# Main.net
KiCad netlist of a schematic drawn in Altium Designer
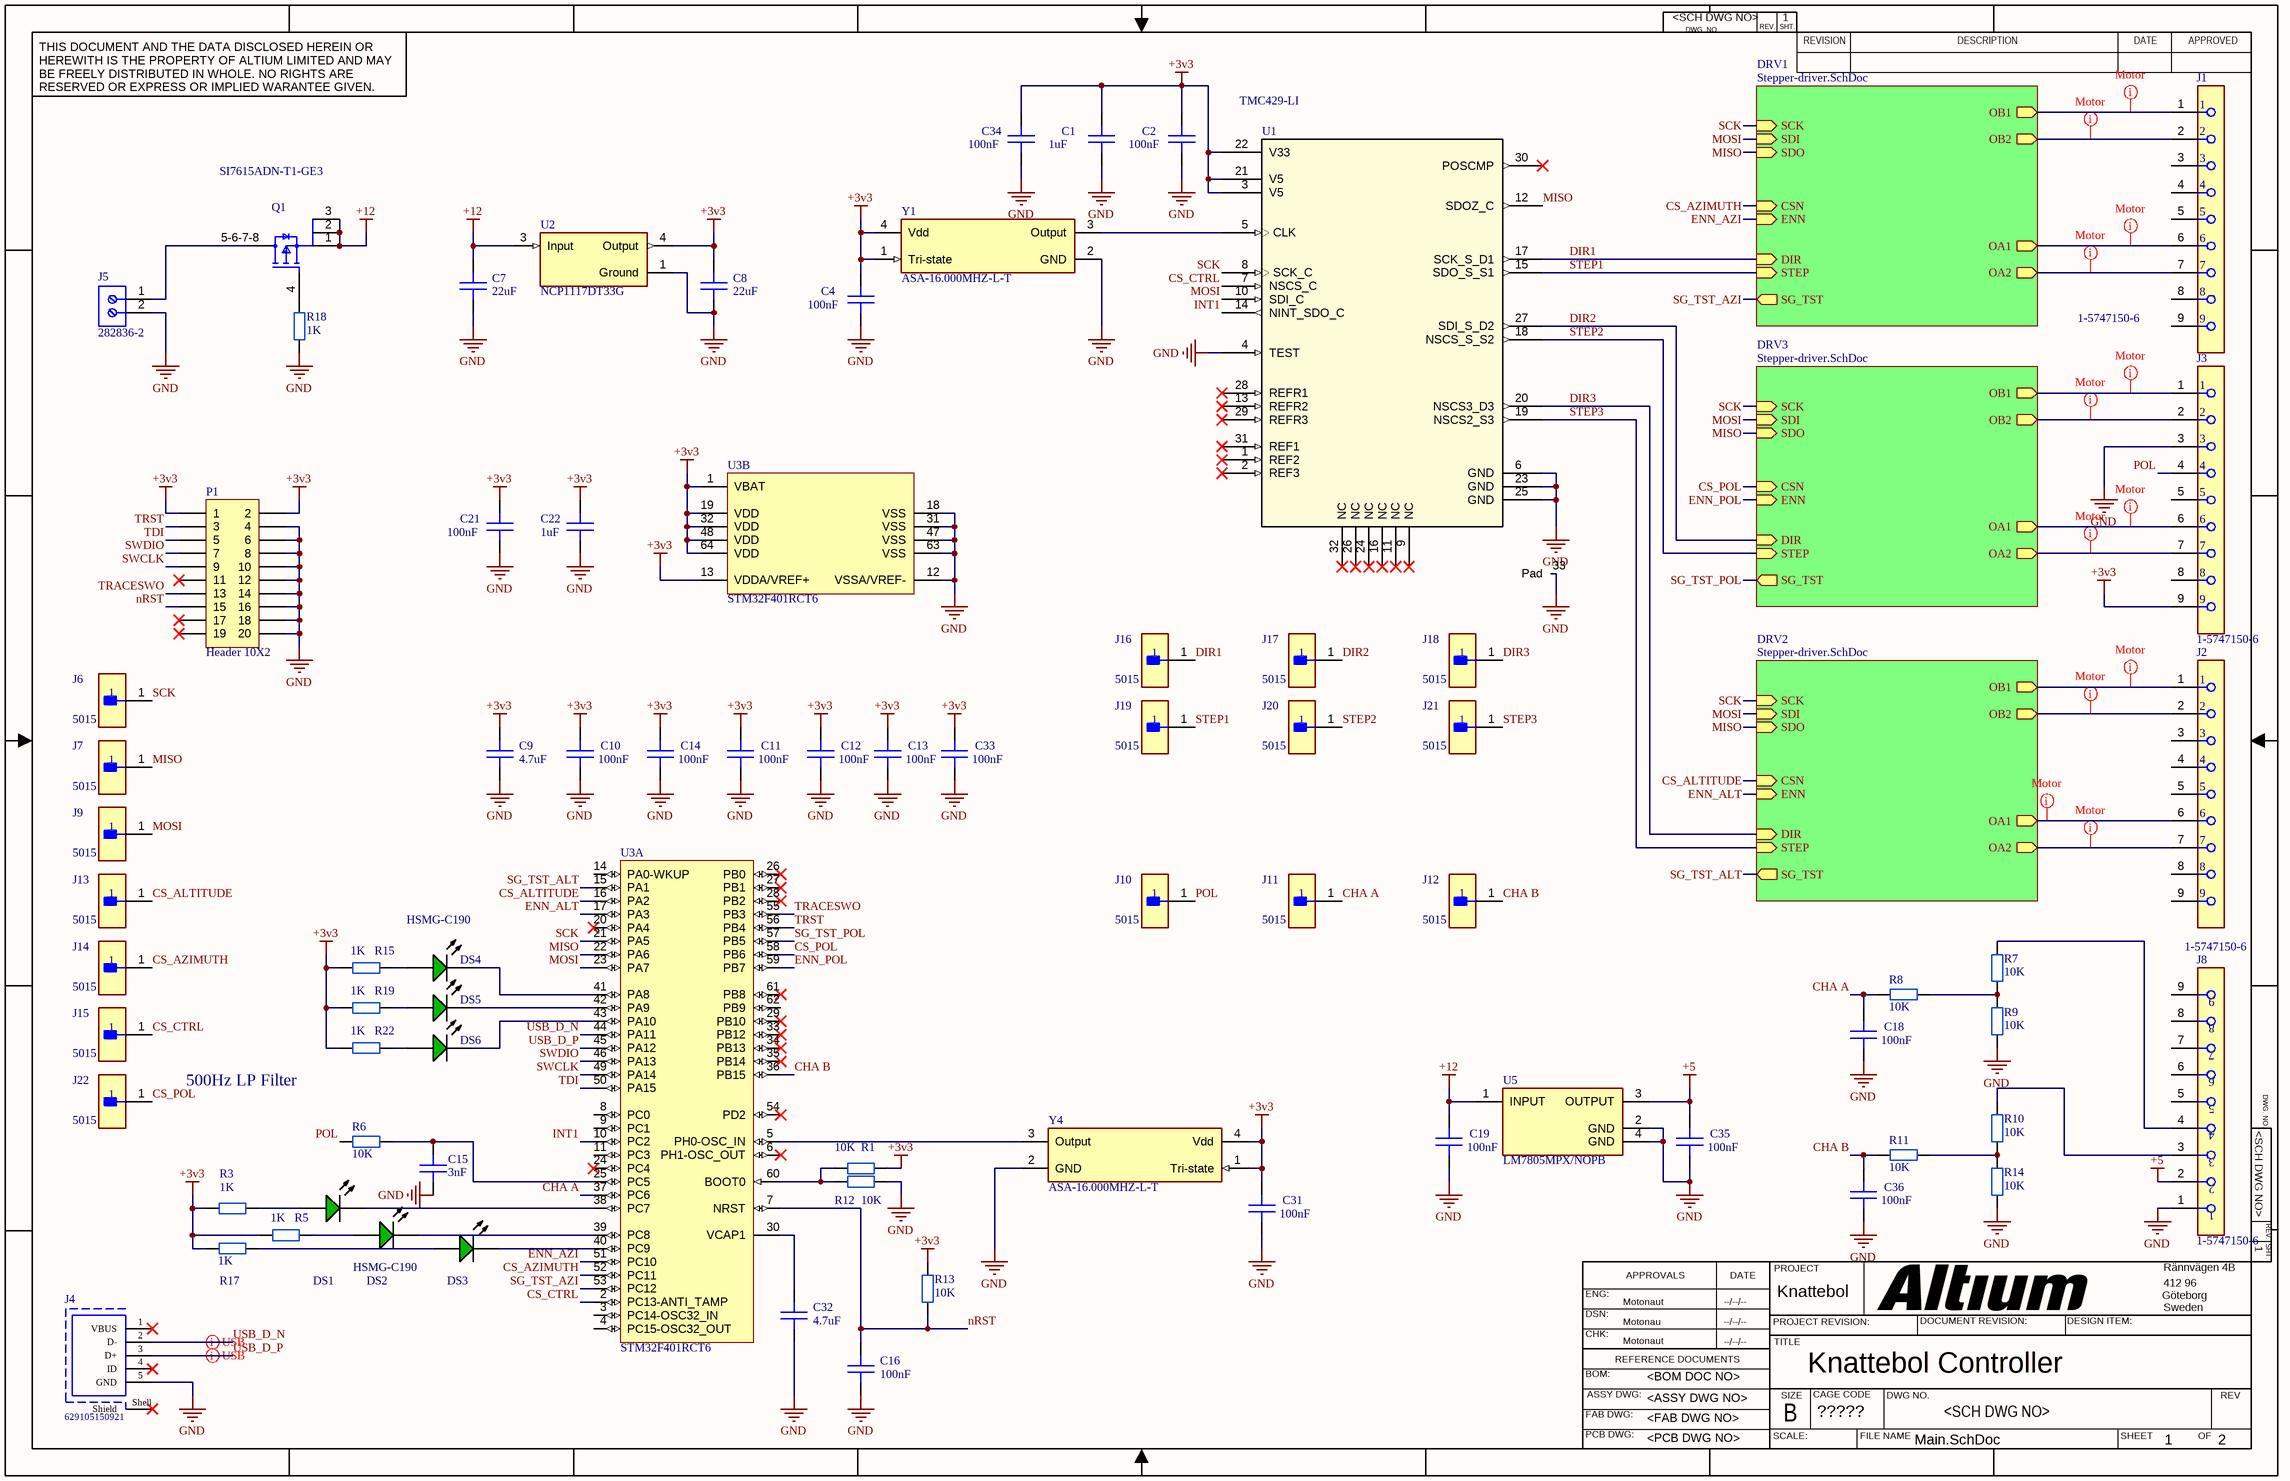
[diagram p0: Main.SchDoc]

(export (version "E")
  (design (tool "Eeschema 10.0.6"))
  (components
    (comp (ref "C1")
      (value "1uF")
      (footprint "C0603 (1608)")
      (fields (field (name "Comment") "Cap SMD"))
      (libsource (lib "Moto Symbol Lib") (part "Cap SMD"))
    )
    (comp (ref "C2")
      (value "100nF")
      (footprint "C0603 (1608)")
      (fields (field (name "Comment") "Cap SMD"))
      (libsource (lib "Moto Symbol Lib") (part "Cap SMD"))
    )
    (comp (ref "C4")
      (value "100nF")
      (footprint "C0603 (1608)")
      (fields (field (name "Comment") "Cap SMD"))
      (libsource (lib "Moto Symbol Lib") (part "Cap SMD"))
    )
    (comp (ref "C7")
      (value "22uF")
      (footprint "C0603 (1608)")
      (fields (field (name "Comment") "Cap SMD"))
      (libsource (lib "Moto Symbol Lib") (part "Cap SMD"))
    )
    (comp (ref "C8")
      (value "22uF")
      (footprint "C0603 (1608)")
      (fields (field (name "Comment") "Cap SMD"))
      (libsource (lib "Moto Symbol Lib") (part "Cap SMD"))
    )
    (comp (ref "C9")
      (value "4.7uF")
      (footprint "C0603 (1608)")
      (fields (field (name "Comment") "Cap SMD"))
      (libsource (lib "Moto Symbol Lib") (part "Cap SMD"))
    )
    (comp (ref "C10")
      (value "100nF")
      (footprint "C0603 (1608)")
      (fields (field (name "Comment") "Cap SMD"))
      (libsource (lib "Moto Symbol Lib") (part "Cap SMD"))
    )
    (comp (ref "C11")
      (value "100nF")
      (footprint "C0603 (1608)")
      (fields (field (name "Comment") "Cap SMD"))
      (libsource (lib "Moto Symbol Lib") (part "Cap SMD"))
    )
    (comp (ref "C12")
      (value "100nF")
      (footprint "C0603 (1608)")
      (fields (field (name "Comment") "Cap SMD"))
      (libsource (lib "Moto Symbol Lib") (part "Cap SMD"))
    )
    (comp (ref "C13")
      (value "100nF")
      (footprint "C0603 (1608)")
      (fields (field (name "Comment") "Cap SMD"))
      (libsource (lib "Moto Symbol Lib") (part "Cap SMD"))
    )
    (comp (ref "C14")
      (value "100nF")
      (footprint "C0603 (1608)")
      (fields (field (name "Comment") "Cap SMD"))
      (libsource (lib "Moto Symbol Lib") (part "Cap SMD"))
    )
    (comp (ref "C15")
      (value "3nF")
      (footprint "C0603 (1608)")
      (fields (field (name "Comment") "Cap SMD"))
      (libsource (lib "Moto Symbol Lib") (part "Cap SMD"))
    )
    (comp (ref "C16")
      (value "100nF")
      (footprint "C0603 (1608)")
      (fields (field (name "Comment") "Cap SMD"))
      (libsource (lib "Moto Symbol Lib") (part "Cap SMD"))
    )
    (comp (ref "C18")
      (value "100nF")
      (footprint "C0603 (1608)")
      (fields (field (name "Comment") "Cap SMD"))
      (libsource (lib "Moto Symbol Lib") (part "Cap SMD"))
    )
    (comp (ref "C19")
      (value "100nF")
      (footprint "C0603 (1608)")
      (fields (field (name "Comment") "Cap SMD"))
      (libsource (lib "Moto Symbol Lib") (part "Cap SMD"))
    )
    (comp (ref "C21")
      (value "100nF")
      (footprint "C0603 (1608)")
      (fields (field (name "Comment") "Cap SMD"))
      (libsource (lib "Moto Symbol Lib") (part "Cap SMD"))
    )
    (comp (ref "C22")
      (value "1uF")
      (footprint "C0603 (1608)")
      (fields (field (name "Comment") "Cap SMD"))
      (libsource (lib "Moto Symbol Lib") (part "Cap SMD"))
    )
    (comp (ref "C31")
      (value "100nF")
      (footprint "C0603 (1608)")
      (fields (field (name "Comment") "Cap SMD"))
      (libsource (lib "Moto Symbol Lib") (part "Cap SMD"))
    )
    (comp (ref "C32")
      (value "4.7uF")
      (footprint "C0603 (1608)")
      (fields (field (name "Comment") "Cap SMD"))
      (libsource (lib "Moto Symbol Lib") (part "Cap SMD"))
    )
    (comp (ref "C33")
      (value "100nF")
      (footprint "C0603 (1608)")
      (fields (field (name "Comment") "Cap SMD"))
      (libsource (lib "Moto Symbol Lib") (part "Cap SMD"))
    )
    (comp (ref "C34")
      (value "100nF")
      (footprint "C0603 (1608)")
      (fields (field (name "Comment") "Cap SMD"))
      (libsource (lib "Moto Symbol Lib") (part "Cap SMD"))
    )
    (comp (ref "C35")
      (value "100nF")
      (footprint "C0603 (1608)")
      (fields (field (name "Comment") "Cap SMD"))
      (libsource (lib "Moto Symbol Lib") (part "Cap SMD"))
    )
    (comp (ref "C36")
      (value "100nF")
      (footprint "C0603 (1608)")
      (fields (field (name "Comment") "Cap SMD"))
      (libsource (lib "Moto Symbol Lib") (part "Cap SMD"))
    )
    (comp (ref "DS1")
      (value "HSMG-C190")
      (footprint "AVAG-HSMX-C190_V")
      (description "Chip LED, Green, 2.2 V, -40 to 85 degC, 2-Pin SMD, RoHS, Tape and Reel")
      (libsource (lib "Altium Content Vault") (part "LED-GREEN-AK-2"))
    )
    (comp (ref "DS2")
      (value "HSMG-C190")
      (footprint "AVAG-HSMX-C190_V")
      (description "Chip LED, Green, 2.2 V, -40 to 85 degC, 2-Pin SMD, RoHS, Tape and Reel")
      (libsource (lib "Altium Content Vault") (part "LED-GREEN-AK-2"))
    )
    (comp (ref "DS3")
      (value "HSMG-C190")
      (footprint "AVAG-HSMX-C190_V")
      (description "Chip LED, Green, 2.2 V, -40 to 85 degC, 2-Pin SMD, RoHS, Tape and Reel")
      (libsource (lib "Altium Content Vault") (part "LED-GREEN-AK-2"))
    )
    (comp (ref "DS4")
      (value "HSMG-C190")
      (footprint "AVAG-HSMX-C190_V")
      (description "Chip LED, Green, 2.2 V, -40 to 85 degC, 2-Pin SMD, RoHS, Tape and Reel")
      (libsource (lib "Altium Content Vault") (part "LED-GREEN-AK-2"))
    )
    (comp (ref "DS5")
      (value "HSMG-C190")
      (footprint "AVAG-HSMX-C190_V")
      (description "Chip LED, Green, 2.2 V, -40 to 85 degC, 2-Pin SMD, RoHS, Tape and Reel")
      (libsource (lib "Altium Content Vault") (part "LED-GREEN-AK-2"))
    )
    (comp (ref "DS6")
      (value "HSMG-C190")
      (footprint "AVAG-HSMX-C190_V")
      (description "Chip LED, Green, 2.2 V, -40 to 85 degC, 2-Pin SMD, RoHS, Tape and Reel")
      (libsource (lib "Altium Content Vault") (part "LED-GREEN-AK-2"))
    )
    (comp (ref "J1")
      (value "1-5747150-6")
      (footprint "FP-1-5747150-6-MFG")
      (description "CONN D-SUB RCPT 9POS VERT SOLDER")
      (fields
        (field (name "OCTOPART") "https://octopart.com/1-5747150-6-te+connectivity-39500344")
        (field (name "MANUFACTURER") "TE Connectivity")
      )
      (libsource (lib "Altium Content Vault") (part "deee9d0d87fff07c08bdfa5b86cd5a5"))
    )
    (comp (ref "J2")
      (value "1-5747150-6")
      (footprint "FP-1-5747150-6-MFG")
      (description "CONN D-SUB RCPT 9POS VERT SOLDER")
      (fields
        (field (name "OCTOPART") "https://octopart.com/1-5747150-6-te+connectivity-39500344")
        (field (name "MANUFACTURER") "TE Connectivity")
      )
      (libsource (lib "Altium Content Vault") (part "deee9d0d87fff07c08bdfa5b86cd5a5"))
    )
    (comp (ref "J3")
      (value "1-5747150-6")
      (footprint "FP-1-5747150-6-MFG")
      (description "CONN D-SUB RCPT 9POS VERT SOLDER")
      (fields
        (field (name "OCTOPART") "https://octopart.com/1-5747150-6-te+connectivity-39500344")
        (field (name "MANUFACTURER") "TE Connectivity")
      )
      (libsource (lib "Altium Content Vault") (part "deee9d0d87fff07c08bdfa5b86cd5a5"))
    )
    (comp (ref "J4")
      (value "629105150921")
      (footprint "629105150921")
      (description "Micro USB 2.0 Type AB Receptacle WR-COM, Horizontal, SMT")
      (fields (field (name "MANUFACTURER") "Wurth Elektronik") (field (name "PUBLISHER") "WurthElektronik"))
      (libsource (lib "Altium Content Vault") (part "WE-USB-5-1SHLD"))
    )
    (comp (ref "J5")
      (value "282836-2")
      (footprint "TECO-282836-2_V")
      (description "Female Header, Pitch 5 mm, 1 x 2 Position, Height 10 mm, Tail Length 3.5 mm, Rohs, Bulk")
      (fields (field (name "VOLTAGE") "300V") (field (name "MANUFACTURER") "TE Connectivity"))
      (libsource (lib "Altium Content Vault") (part "CN-1P-F-TB2"))
    )
    (comp (ref "J6")
      (value "5015")
      (footprint "FP-5015-MFG")
      (description "PC TEST POINT MINIATURE")
      (fields
        (field (name "MANUFACTURER") "keystone")
        (field (name "OCTOPART") "https://octopart.com/5015-keystone-3822")
      )
      (libsource (lib "Altium Content Vault") (part "dd45045ce8184df9e99e12baf3f412c"))
    )
    (comp (ref "J7")
      (value "5015")
      (footprint "FP-5015-MFG")
      (description "PC TEST POINT MINIATURE")
      (fields
        (field (name "MANUFACTURER") "keystone")
        (field (name "OCTOPART") "https://octopart.com/5015-keystone-3822")
      )
      (libsource (lib "Altium Content Vault") (part "dd45045ce8184df9e99e12baf3f412c"))
    )
    (comp (ref "J8")
      (value "1-5747150-6")
      (footprint "FP-1-5747150-6-MFG")
      (description "CONN D-SUB RCPT 9POS VERT SOLDER")
      (fields
        (field (name "OCTOPART") "https://octopart.com/1-5747150-6-te+connectivity-39500344")
        (field (name "MANUFACTURER") "TE Connectivity")
      )
      (libsource (lib "") (part "deee9d0d87fff07c08bdfa5b86cd5a5_1"))
    )
    (comp (ref "J9")
      (value "5015")
      (footprint "FP-5015-MFG")
      (description "PC TEST POINT MINIATURE")
      (fields
        (field (name "MANUFACTURER") "keystone")
        (field (name "OCTOPART") "https://octopart.com/5015-keystone-3822")
      )
      (libsource (lib "Altium Content Vault") (part "dd45045ce8184df9e99e12baf3f412c"))
    )
    (comp (ref "J10")
      (value "5015")
      (footprint "FP-5015-MFG")
      (description "PC TEST POINT MINIATURE")
      (fields
        (field (name "MANUFACTURER") "keystone")
        (field (name "OCTOPART") "https://octopart.com/5015-keystone-3822")
      )
      (libsource (lib "Altium Content Vault") (part "dd45045ce8184df9e99e12baf3f412c"))
    )
    (comp (ref "J11")
      (value "5015")
      (footprint "FP-5015-MFG")
      (description "PC TEST POINT MINIATURE")
      (fields
        (field (name "MANUFACTURER") "keystone")
        (field (name "OCTOPART") "https://octopart.com/5015-keystone-3822")
      )
      (libsource (lib "Altium Content Vault") (part "dd45045ce8184df9e99e12baf3f412c"))
    )
    (comp (ref "J12")
      (value "5015")
      (footprint "FP-5015-MFG")
      (description "PC TEST POINT MINIATURE")
      (fields
        (field (name "MANUFACTURER") "keystone")
        (field (name "OCTOPART") "https://octopart.com/5015-keystone-3822")
      )
      (libsource (lib "Altium Content Vault") (part "dd45045ce8184df9e99e12baf3f412c"))
    )
    (comp (ref "J13")
      (value "5015")
      (footprint "FP-5015-MFG")
      (description "PC TEST POINT MINIATURE")
      (fields
        (field (name "MANUFACTURER") "keystone")
        (field (name "OCTOPART") "https://octopart.com/5015-keystone-3822")
      )
      (libsource (lib "Altium Content Vault") (part "dd45045ce8184df9e99e12baf3f412c"))
    )
    (comp (ref "J14")
      (value "5015")
      (footprint "FP-5015-MFG")
      (description "PC TEST POINT MINIATURE")
      (fields
        (field (name "MANUFACTURER") "keystone")
        (field (name "OCTOPART") "https://octopart.com/5015-keystone-3822")
      )
      (libsource (lib "Altium Content Vault") (part "dd45045ce8184df9e99e12baf3f412c"))
    )
    (comp (ref "J15")
      (value "5015")
      (footprint "FP-5015-MFG")
      (description "PC TEST POINT MINIATURE")
      (fields
        (field (name "MANUFACTURER") "keystone")
        (field (name "OCTOPART") "https://octopart.com/5015-keystone-3822")
      )
      (libsource (lib "Altium Content Vault") (part "dd45045ce8184df9e99e12baf3f412c"))
    )
    (comp (ref "J16")
      (value "5015")
      (footprint "FP-5015-MFG")
      (description "PC TEST POINT MINIATURE")
      (fields
        (field (name "MANUFACTURER") "keystone")
        (field (name "OCTOPART") "https://octopart.com/5015-keystone-3822")
      )
      (libsource (lib "Altium Content Vault") (part "dd45045ce8184df9e99e12baf3f412c"))
    )
    (comp (ref "J17")
      (value "5015")
      (footprint "FP-5015-MFG")
      (description "PC TEST POINT MINIATURE")
      (fields
        (field (name "MANUFACTURER") "keystone")
        (field (name "OCTOPART") "https://octopart.com/5015-keystone-3822")
      )
      (libsource (lib "Altium Content Vault") (part "dd45045ce8184df9e99e12baf3f412c"))
    )
    (comp (ref "J18")
      (value "5015")
      (footprint "FP-5015-MFG")
      (description "PC TEST POINT MINIATURE")
      (fields
        (field (name "MANUFACTURER") "keystone")
        (field (name "OCTOPART") "https://octopart.com/5015-keystone-3822")
      )
      (libsource (lib "Altium Content Vault") (part "dd45045ce8184df9e99e12baf3f412c"))
    )
    (comp (ref "J19")
      (value "5015")
      (footprint "FP-5015-MFG")
      (description "PC TEST POINT MINIATURE")
      (fields
        (field (name "MANUFACTURER") "keystone")
        (field (name "OCTOPART") "https://octopart.com/5015-keystone-3822")
      )
      (libsource (lib "Altium Content Vault") (part "dd45045ce8184df9e99e12baf3f412c"))
    )
    (comp (ref "J20")
      (value "5015")
      (footprint "FP-5015-MFG")
      (description "PC TEST POINT MINIATURE")
      (fields
        (field (name "MANUFACTURER") "keystone")
        (field (name "OCTOPART") "https://octopart.com/5015-keystone-3822")
      )
      (libsource (lib "Altium Content Vault") (part "dd45045ce8184df9e99e12baf3f412c"))
    )
    (comp (ref "J21")
      (value "5015")
      (footprint "FP-5015-MFG")
      (description "PC TEST POINT MINIATURE")
      (fields
        (field (name "MANUFACTURER") "keystone")
        (field (name "OCTOPART") "https://octopart.com/5015-keystone-3822")
      )
      (libsource (lib "Altium Content Vault") (part "dd45045ce8184df9e99e12baf3f412c"))
    )
    (comp (ref "J22")
      (value "5015")
      (footprint "FP-5015-MFG")
      (description "PC TEST POINT MINIATURE")
      (fields
        (field (name "MANUFACTURER") "keystone")
        (field (name "OCTOPART") "https://octopart.com/5015-keystone-3822")
      )
      (libsource (lib "Altium Content Vault") (part "dd45045ce8184df9e99e12baf3f412c"))
    )
    (comp (ref "P1")
      (value "Header 10X2")
      (footprint "HDR2X10")
      (description "Header, 10-Pin, Dual row")
      (fields (field (name "PUBLISHER") "Altium Limited"))
      (libsource (lib "Miscellaneous Connectors") (part "Header 10X2"))
    )
    (comp (ref "Q1")
      (value "SI7615ADN-T1-GE3")
      (footprint "FP-S16-2667_SINGLE-MFG")
      (description "MOSFET P-CH 20V 35A 1212-8S")
      (fields
        (field (name "OCTOPART") "https://octopart.com/si7615adn-t1-ge3-vishay-45331111")
        (field (name "MANUFACTURER") "Vishay")
      )
      (libsource (lib "Altium Content Vault") (part "2fcdebc9db46997103ded74af620a28"))
    )
    (comp (ref "R1")
      (value "10K")
      (footprint "R0603 (1608)")
      (libsource (lib "Moto Symbol Lib") (part "Resistor EU"))
    )
    (comp (ref "R3")
      (value "1K")
      (footprint "R0603 (1608)")
      (libsource (lib "Moto Symbol Lib") (part "Resistor EU"))
    )
    (comp (ref "R5")
      (value "1K")
      (footprint "R0603 (1608)")
      (libsource (lib "Moto Symbol Lib") (part "Resistor EU"))
    )
    (comp (ref "R6")
      (value "10K")
      (footprint "R0603 (1608)")
      (libsource (lib "Moto Symbol Lib") (part "Resistor EU"))
    )
    (comp (ref "R7")
      (value "10K")
      (footprint "R0603 (1608)")
      (libsource (lib "Moto Symbol Lib") (part "Resistor EU"))
    )
    (comp (ref "R8")
      (value "10K")
      (footprint "R0603 (1608)")
      (libsource (lib "Moto Symbol Lib") (part "Resistor EU"))
    )
    (comp (ref "R9")
      (value "10K")
      (footprint "R0603 (1608)")
      (libsource (lib "Moto Symbol Lib") (part "Resistor EU"))
    )
    (comp (ref "R10")
      (value "10K")
      (footprint "R0603 (1608)")
      (libsource (lib "Moto Symbol Lib") (part "Resistor EU"))
    )
    (comp (ref "R11")
      (value "10K")
      (footprint "R0603 (1608)")
      (libsource (lib "Moto Symbol Lib") (part "Resistor EU"))
    )
    (comp (ref "R12")
      (value "10K")
      (footprint "R0603 (1608)")
      (libsource (lib "Moto Symbol Lib") (part "Resistor EU"))
    )
    (comp (ref "R13")
      (value "10K")
      (footprint "R0603 (1608)")
      (libsource (lib "Moto Symbol Lib") (part "Resistor EU"))
    )
    (comp (ref "R14")
      (value "10K")
      (footprint "R0603 (1608)")
      (libsource (lib "Moto Symbol Lib") (part "Resistor EU"))
    )
    (comp (ref "R15")
      (value "1K")
      (footprint "R0603 (1608)")
      (libsource (lib "Moto Symbol Lib") (part "Resistor EU"))
    )
    (comp (ref "R17")
      (value "1K")
      (footprint "R0603 (1608)")
      (libsource (lib "Moto Symbol Lib") (part "Resistor EU"))
    )
    (comp (ref "R18")
      (value "1K")
      (footprint "R0603 (1608)")
      (libsource (lib "Moto Symbol Lib") (part "Resistor EU"))
    )
    (comp (ref "R19")
      (value "1K")
      (footprint "R0603 (1608)")
      (libsource (lib "Moto Symbol Lib") (part "Resistor EU"))
    )
    (comp (ref "R22")
      (value "1K")
      (footprint "R0603 (1608)")
      (libsource (lib "Moto Symbol Lib") (part "Resistor EU"))
    )
    (comp (ref "U1")
      (value "TMC429-LI")
      (footprint "QFN32_5X5_TRI-M")
      (description "No Description Available")
      (fields (field (name "COPYRIGHT") "Copyright (C) 2016 Accelerated Designs. All rights reserved"))
      (libsource (lib "Moto Symbol Lib") (part "TMC429-LI"))
    )
    (comp (ref "U2")
      (value "NCP1117DT33G")
      (footprint "FP-369C-MFG")
      (description "IC REG LINEAR 3.3V 1A DPAK")
      (fields
        (field (name "MANUFACTURER") "ON Semiconductor")
        (field (name "OCTOPART") "https://octopart.com/ncp1117dt33g-on+semiconductor-1381653")
      )
      (libsource (lib "Altium Content Vault") (part "5c9640907b51bf2d298b9e653f26f2d"))
    )
    (comp (ref "U3")
      (value "STM32F401RCT6")
      (footprint "STM-LQFP64_M")
      (fields (field (name "MANUFACTURER") "STMicroelectronics"))
      (libsource (lib "Altium Content Vault") (part "MC-ARM-STM32F401-SQ64"))
    )
    (comp (ref "U5")
      (value "LM7805MPX/NOPB")
      (footprint "FP-LM7805MPX-NOPB-MFG")
      (description "IC REG LINEAR 5V 1.5A SOT223-4")
      (fields
        (field (name "MANUFACTURER") "Texas Instruments")
        (field (name "OCTOPART") "https://octopart.com/lm7805mpx%2Fnopb-texas+instruments-74629992")
      )
      (libsource (lib "Altium Content Vault") (part "b4ee7691a89d8e73302b24c49f391f2"))
    )
    (comp (ref "Y1")
      (value "ASA-16.000MHZ-L-T")
      (footprint "FP-ASA-MFG")
      (description "XTAL OSC XO 16.0000MHZ HCMOS SMD")
      (fields
        (field (name "OCTOPART") "https://octopart.com/asa-16.000mhz-l-t-abracon-21707822")
        (field (name "MANUFACTURER") "Abracon")
      )
      (libsource (lib "") (part "7c953fa1d91b086b7cda9813af2bec8_1"))
    )
    (comp (ref "Y4")
      (value "ASA-16.000MHZ-L-T")
      (footprint "FP-ASA-MFG")
      (description "XTAL OSC XO 16.0000MHZ HCMOS SMD")
      (fields
        (field (name "OCTOPART") "https://octopart.com/asa-16.000mhz-l-t-abracon-21707822")
        (field (name "MANUFACTURER") "Abracon")
      )
      (libsource (lib "Altium Content Vault") (part "7c953fa1d91b086b7cda9813af2bec8"))
    )
  )
  (nets
    (net (code "1") (name "+3v3") (class "Default")
      (node (ref "C1") (pin "2") (pinfunction "2_2") (pintype "power_in"))
      (node (ref "C10") (pin "2") (pinfunction "2_2") (pintype "power_in"))
      (node (ref "C11") (pin "2") (pinfunction "2_2") (pintype "power_in"))
      (node (ref "C12") (pin "2") (pinfunction "2_2") (pintype "power_in"))
      (node (ref "C13") (pin "2") (pinfunction "2_2") (pintype "power_in"))
      (node (ref "C14") (pin "2") (pinfunction "2_2") (pintype "power_in"))
      (node (ref "C2") (pin "2") (pinfunction "2_2") (pintype "power_in"))
      (node (ref "C21") (pin "2") (pinfunction "2_2") (pintype "power_in"))
      (node (ref "C22") (pin "2") (pinfunction "2_2") (pintype "power_in"))
      (node (ref "C31") (pin "2") (pinfunction "2_2") (pintype "power_in"))
      (node (ref "C33") (pin "2") (pinfunction "2_2") (pintype "power_in"))
      (node (ref "C34") (pin "2") (pinfunction "2_2") (pintype "power_in"))
      (node (ref "C4") (pin "2") (pinfunction "2_2") (pintype "power_in"))
      (node (ref "C8") (pin "2") (pinfunction "2_2") (pintype "power_in"))
      (node (ref "C9") (pin "2") (pinfunction "2_2") (pintype "power_in"))
      (node (ref "J3") (pin "9") (pinfunction "9_9") (pintype "passive"))
      (node (ref "P1") (pin "1") (pinfunction "1_1") (pintype "passive"))
      (node (ref "P1") (pin "2") (pinfunction "2_2") (pintype "passive"))
      (node (ref "R1") (pin "2") (pinfunction "2_2") (pintype "power_in"))
      (node (ref "R13") (pin "2") (pinfunction "2_2") (pintype "power_in"))
      (node (ref "R15") (pin "1") (pinfunction "1_1") (pintype "power_in"))
      (node (ref "R17") (pin "1") (pinfunction "1_1") (pintype "power_in"))
      (node (ref "R19") (pin "1") (pinfunction "1_1") (pintype "power_in"))
      (node (ref "R22") (pin "1") (pinfunction "1_1") (pintype "power_in"))
      (node (ref "R3") (pin "1") (pinfunction "1_1") (pintype "power_in"))
      (node (ref "R5") (pin "1") (pinfunction "1_1") (pintype "power_in"))
      (node (ref "U1") (pin "21") (pinfunction "V5_21") (pintype "power_in"))
      (node (ref "U1") (pin "22") (pinfunction "V33_22") (pintype "power_in"))
      (node (ref "U1") (pin "3") (pinfunction "V5_3") (pintype "power_in"))
      (node (ref "U2") (pin "4") (pinfunction "Output_4") (pintype "output"))
      (node (ref "U3") (pin "1") (pinfunction "VBAT_1") (pintype "power_in"))
      (node (ref "U3") (pin "13") (pinfunction "VDDA/VREF+_13") (pintype "power_in"))
      (node (ref "U3") (pin "19") (pinfunction "VDD_19") (pintype "power_in"))
      (node (ref "U3") (pin "32") (pinfunction "VDD_32") (pintype "power_in"))
      (node (ref "U3") (pin "48") (pinfunction "VDD_48") (pintype "power_in"))
      (node (ref "U3") (pin "64") (pinfunction "VDD_64") (pintype "power_in"))
      (node (ref "Y1") (pin "1") (pinfunction "Tri-state_1") (pintype "input"))
      (node (ref "Y1") (pin "4") (pinfunction "Vdd_4") (pintype "power_in"))
      (node (ref "Y4") (pin "1") (pinfunction "Tri-state_1") (pintype "input"))
      (node (ref "Y4") (pin "4") (pinfunction "Vdd_4") (pintype "power_in"))
    )
    (net (code "2") (name "+5") (class "Default")
      (node (ref "C35") (pin "2") (pinfunction "2_2") (pintype "power_in"))
      (node (ref "J8") (pin "2") (pinfunction "2_2") (pintype "passive"))
      (node (ref "U5") (pin "3") (pinfunction "OUTPUT_3") (pintype "passive"))
    )
    (net (code "3") (name "+12") (class "Default")
      (node (ref "C19") (pin "2") (pinfunction "2_2") (pintype "power_in"))
      (node (ref "C7") (pin "2") (pinfunction "2_2") (pintype "power_in"))
      (node (ref "Q1") (pin "1") (pinfunction "S_1") (pintype "passive"))
      (node (ref "Q1") (pin "2") (pinfunction "S_2") (pintype "passive"))
      (node (ref "Q1") (pin "3") (pinfunction "S_3") (pintype "passive"))
      (node (ref "U2") (pin "3") (pinfunction "Input_3") (pintype "input"))
      (node (ref "U5") (pin "1") (pinfunction "INPUT_1") (pintype "power_in"))
    )
    (net (code "4") (name "/CHA A") (class "Default")
      (node (ref "C18") (pin "2") (pinfunction "2_2") (pintype "power_in"))
      (node (ref "J11") (pin "1") (pinfunction "1_1") (pintype "passive"))
      (node (ref "R8") (pin "2") (pinfunction "2_2") (pintype "power_in"))
      (node (ref "U3") (pin "37") (pinfunction "PC6_37") (pintype "bidirectional"))
    )
    (net (code "5") (name "/CHA B") (class "Default")
      (node (ref "C36") (pin "2") (pinfunction "2_2") (pintype "power_in"))
      (node (ref "J12") (pin "1") (pinfunction "1_1") (pintype "passive"))
      (node (ref "R11") (pin "2") (pinfunction "2_2") (pintype "power_in"))
      (node (ref "U3") (pin "36") (pinfunction "PB15_36") (pintype "bidirectional"))
    )
    (net (code "6") (name "/CS_ALTITUDE") (class "Default")
      (node (ref "J13") (pin "1") (pinfunction "1_1") (pintype "passive"))
      (node (ref "U3") (pin "16") (pinfunction "PA2_16") (pintype "bidirectional"))
    )
    (net (code "7") (name "/CS_AZIMUTH") (class "Default")
      (node (ref "J14") (pin "1") (pinfunction "1_1") (pintype "passive"))
      (node (ref "U3") (pin "52") (pinfunction "PC11_52") (pintype "bidirectional"))
    )
    (net (code "8") (name "/CS_CTRL") (class "Default")
      (node (ref "J15") (pin "1") (pinfunction "1_1") (pintype "passive"))
      (node (ref "U1") (pin "7") (pinfunction "NSCS_C_7") (pintype "input"))
      (node (ref "U3") (pin "2") (pinfunction "PC13-ANTI_TAMP_2") (pintype "bidirectional"))
    )
    (net (code "9") (name "/CS_POL") (class "Default")
      (node (ref "J22") (pin "1") (pinfunction "1_1") (pintype "passive"))
      (node (ref "U3") (pin "58") (pinfunction "PB6_58") (pintype "bidirectional"))
    )
    (net (code "10") (name "/DIR1") (class "Default")
      (node (ref "J16") (pin "1") (pinfunction "1_1") (pintype "passive"))
      (node (ref "U1") (pin "17") (pinfunction "SCK_S_D1_17") (pintype "output"))
    )
    (net (code "11") (name "/DIR2") (class "Default")
      (node (ref "J17") (pin "1") (pinfunction "1_1") (pintype "passive"))
      (node (ref "U1") (pin "27") (pinfunction "SDI_S_D2_27") (pintype "output"))
    )
    (net (code "12") (name "/DIR3") (class "Default")
      (node (ref "J18") (pin "1") (pinfunction "1_1") (pintype "passive"))
      (node (ref "U1") (pin "20") (pinfunction "NSCS3_D3_20") (pintype "output"))
    )
    (net (code "13") (name "/ENN_ALT") (class "Default")
      (node (ref "U3") (pin "17") (pinfunction "PA3_17") (pintype "bidirectional"))
    )
    (net (code "14") (name "/ENN_AZI") (class "Default")
      (node (ref "U3") (pin "51") (pinfunction "PC10_51") (pintype "bidirectional"))
    )
    (net (code "15") (name "/ENN_POL") (class "Default")
      (node (ref "U3") (pin "59") (pinfunction "PB7_59") (pintype "bidirectional"))
    )
    (net (code "16") (name "/INT1") (class "Default")
      (node (ref "U1") (pin "14") (pinfunction "NINT_SDO_C_14") (pintype "output"))
      (node (ref "U3") (pin "10") (pinfunction "PC2_10") (pintype "bidirectional"))
    )
    (net (code "17") (name "/MISO") (class "Default")
      (node (ref "J7") (pin "1") (pinfunction "1_1") (pintype "passive"))
      (node (ref "U1") (pin "12") (pinfunction "SDOZ_C_12") (pintype "output"))
      (node (ref "U3") (pin "22") (pinfunction "PA6_22") (pintype "bidirectional"))
    )
    (net (code "18") (name "/MOSI") (class "Default")
      (node (ref "J9") (pin "1") (pinfunction "1_1") (pintype "passive"))
      (node (ref "U1") (pin "10") (pinfunction "SDI_C_10") (pintype "input"))
      (node (ref "U3") (pin "23") (pinfunction "PA7_23") (pintype "bidirectional"))
    )
    (net (code "19") (name "/OA1") (class "Default")
      (node (ref "J3") (pin "6") (pinfunction "6_6") (pintype "passive"))
    )
    (net (code "20") (name "/OA1_1") (class "Default")
      (node (ref "J2") (pin "6") (pinfunction "6_6") (pintype "passive"))
    )
    (net (code "21") (name "/OA1_2") (class "Default")
      (node (ref "J1") (pin "6") (pinfunction "6_6") (pintype "passive"))
    )
    (net (code "22") (name "/OA2") (class "Default")
      (node (ref "J3") (pin "7") (pinfunction "7_7") (pintype "passive"))
    )
    (net (code "23") (name "/OA2_1") (class "Default")
      (node (ref "J2") (pin "7") (pinfunction "7_7") (pintype "passive"))
    )
    (net (code "24") (name "/OA2_2") (class "Default")
      (node (ref "J1") (pin "7") (pinfunction "7_7") (pintype "passive"))
    )
    (net (code "25") (name "/OB1") (class "Default")
      (node (ref "J2") (pin "1") (pinfunction "1_1") (pintype "passive"))
    )
    (net (code "26") (name "/OB1_1") (class "Default")
      (node (ref "J1") (pin "1") (pinfunction "1_1") (pintype "passive"))
    )
    (net (code "27") (name "/OB1_2") (class "Default")
      (node (ref "J3") (pin "1") (pinfunction "1_1") (pintype "passive"))
    )
    (net (code "28") (name "/OB2") (class "Default")
      (node (ref "J2") (pin "2") (pinfunction "2_2") (pintype "passive"))
    )
    (net (code "29") (name "/OB2_1") (class "Default")
      (node (ref "J1") (pin "2") (pinfunction "2_2") (pintype "passive"))
    )
    (net (code "30") (name "/OB2_2") (class "Default")
      (node (ref "J3") (pin "2") (pinfunction "2_2") (pintype "passive"))
    )
    (net (code "31") (name "/POL") (class "Default")
      (node (ref "J10") (pin "1") (pinfunction "1_1") (pintype "passive"))
      (node (ref "J3") (pin "4") (pinfunction "4_4") (pintype "passive"))
      (node (ref "R6") (pin "1") (pinfunction "1_1") (pintype "power_in"))
    )
    (net (code "32") (name "/SCK") (class "Default")
      (node (ref "J6") (pin "1") (pinfunction "1_1") (pintype "passive"))
      (node (ref "U1") (pin "8") (pinfunction "SCK_C_8") (pintype "input"))
      (node (ref "U3") (pin "21") (pinfunction "PA5_21") (pintype "bidirectional"))
    )
    (net (code "33") (name "/SG_TST_ALT") (class "Default")
      (node (ref "U3") (pin "15") (pinfunction "PA1_15") (pintype "bidirectional"))
    )
    (net (code "34") (name "/SG_TST_AZI") (class "Default")
      (node (ref "U3") (pin "53") (pinfunction "PC12_53") (pintype "bidirectional"))
    )
    (net (code "35") (name "/SG_TST_POL") (class "Default")
      (node (ref "U3") (pin "57") (pinfunction "PB5_57") (pintype "bidirectional"))
    )
    (net (code "36") (name "/STEP1") (class "Default")
      (node (ref "J19") (pin "1") (pinfunction "1_1") (pintype "passive"))
      (node (ref "U1") (pin "15") (pinfunction "SDO_S_S1_15") (pintype "output"))
    )
    (net (code "37") (name "/STEP2") (class "Default")
      (node (ref "J20") (pin "1") (pinfunction "1_1") (pintype "passive"))
      (node (ref "U1") (pin "18") (pinfunction "NSCS_S_S2_18") (pintype "output"))
    )
    (net (code "38") (name "/STEP3") (class "Default")
      (node (ref "J21") (pin "1") (pinfunction "1_1") (pintype "passive"))
      (node (ref "U1") (pin "19") (pinfunction "NSCS2_S3_19") (pintype "output"))
    )
    (net (code "39") (name "/SWCLK") (class "Default")
      (node (ref "P1") (pin "9") (pinfunction "9_9") (pintype "passive"))
      (node (ref "U3") (pin "49") (pinfunction "PA14_49") (pintype "bidirectional"))
    )
    (net (code "40") (name "/SWDIO") (class "Default")
      (node (ref "P1") (pin "7") (pinfunction "7_7") (pintype "passive"))
      (node (ref "U3") (pin "46") (pinfunction "PA13_46") (pintype "bidirectional"))
    )
    (net (code "41") (name "/TDI") (class "Default")
      (node (ref "P1") (pin "5") (pinfunction "5_5") (pintype "passive"))
      (node (ref "U3") (pin "50") (pinfunction "PA15_50") (pintype "bidirectional"))
    )
    (net (code "42") (name "/TRACESWO") (class "Default")
      (node (ref "P1") (pin "13") (pinfunction "13_13") (pintype "passive"))
      (node (ref "U3") (pin "55") (pinfunction "PB3_55") (pintype "bidirectional"))
    )
    (net (code "43") (name "/TRST") (class "Default")
      (node (ref "P1") (pin "3") (pinfunction "3_3") (pintype "passive"))
      (node (ref "U3") (pin "56") (pinfunction "PB4_56") (pintype "bidirectional"))
    )
    (net (code "44") (name "/USB_D_N") (class "Default")
      (node (ref "J4") (pin "2") (pinfunction "D-_2") (pintype "passive"))
      (node (ref "U3") (pin "44") (pinfunction "PA11_44") (pintype "bidirectional"))
    )
    (net (code "45") (name "/USB_D_P") (class "Default")
      (node (ref "J4") (pin "3") (pinfunction "D+_3") (pintype "passive"))
      (node (ref "U3") (pin "45") (pinfunction "PA12_45") (pintype "bidirectional"))
    )
    (net (code "46") (name "/nRST") (class "Default")
      (node (ref "C16") (pin "2") (pinfunction "2_2") (pintype "power_in"))
      (node (ref "P1") (pin "15") (pinfunction "15_15") (pintype "passive"))
      (node (ref "R13") (pin "1") (pinfunction "1_1") (pintype "power_in"))
      (node (ref "U3") (pin "7") (pinfunction "NRST_7") (pintype "bidirectional"))
    )
    (net (code "47") (name "GND") (class "Default")
      (node (ref "C1") (pin "1") (pinfunction "1_1") (pintype "power_in"))
      (node (ref "C10") (pin "1") (pinfunction "1_1") (pintype "power_in"))
      (node (ref "C11") (pin "1") (pinfunction "1_1") (pintype "power_in"))
      (node (ref "C12") (pin "1") (pinfunction "1_1") (pintype "power_in"))
      (node (ref "C13") (pin "1") (pinfunction "1_1") (pintype "power_in"))
      (node (ref "C14") (pin "1") (pinfunction "1_1") (pintype "power_in"))
      (node (ref "C15") (pin "1") (pinfunction "1_1") (pintype "power_in"))
      (node (ref "C16") (pin "1") (pinfunction "1_1") (pintype "power_in"))
      (node (ref "C18") (pin "1") (pinfunction "1_1") (pintype "power_in"))
      (node (ref "C19") (pin "1") (pinfunction "1_1") (pintype "power_in"))
      (node (ref "C2") (pin "1") (pinfunction "1_1") (pintype "power_in"))
      (node (ref "C21") (pin "1") (pinfunction "1_1") (pintype "power_in"))
      (node (ref "C22") (pin "1") (pinfunction "1_1") (pintype "power_in"))
      (node (ref "C31") (pin "1") (pinfunction "1_1") (pintype "power_in"))
      (node (ref "C32") (pin "1") (pinfunction "1_1") (pintype "power_in"))
      (node (ref "C33") (pin "1") (pinfunction "1_1") (pintype "power_in"))
      (node (ref "C34") (pin "1") (pinfunction "1_1") (pintype "power_in"))
      (node (ref "C35") (pin "1") (pinfunction "1_1") (pintype "power_in"))
      (node (ref "C36") (pin "1") (pinfunction "1_1") (pintype "power_in"))
      (node (ref "C4") (pin "1") (pinfunction "1_1") (pintype "power_in"))
      (node (ref "C7") (pin "1") (pinfunction "1_1") (pintype "power_in"))
      (node (ref "C8") (pin "1") (pinfunction "1_1") (pintype "power_in"))
      (node (ref "C9") (pin "1") (pinfunction "1_1") (pintype "power_in"))
      (node (ref "J3") (pin "3") (pinfunction "3_3") (pintype "passive"))
      (node (ref "J4") (pin "5") (pinfunction "GND_5") (pintype "passive"))
      (node (ref "J5") (pin "2") (pinfunction "2_2") (pintype "passive"))
      (node (ref "J8") (pin "1") (pinfunction "1_1") (pintype "passive"))
      (node (ref "P1") (pin "10") (pinfunction "10_10") (pintype "passive"))
      (node (ref "P1") (pin "12") (pinfunction "12_12") (pintype "passive"))
      (node (ref "P1") (pin "14") (pinfunction "14_14") (pintype "passive"))
      (node (ref "P1") (pin "16") (pinfunction "16_16") (pintype "passive"))
      (node (ref "P1") (pin "18") (pinfunction "18_18") (pintype "passive"))
      (node (ref "P1") (pin "20") (pinfunction "20_20") (pintype "passive"))
      (node (ref "P1") (pin "4") (pinfunction "4_4") (pintype "passive"))
      (node (ref "P1") (pin "6") (pinfunction "6_6") (pintype "passive"))
      (node (ref "P1") (pin "8") (pinfunction "8_8") (pintype "passive"))
      (node (ref "R12") (pin "2") (pinfunction "2_2") (pintype "power_in"))
      (node (ref "R14") (pin "1") (pinfunction "1_1") (pintype "power_in"))
      (node (ref "R18") (pin "1") (pinfunction "1_1") (pintype "power_in"))
      (node (ref "R9") (pin "1") (pinfunction "1_1") (pintype "power_in"))
      (node (ref "U1") (pin "23") (pinfunction "GND_23") (pintype "power_in"))
      (node (ref "U1") (pin "25") (pinfunction "GND_25") (pintype "power_in"))
      (node (ref "U1") (pin "33") (pinfunction "Pad_33") (pintype "power_in"))
      (node (ref "U1") (pin "4") (pinfunction "TEST_4") (pintype "input"))
      (node (ref "U1") (pin "6") (pinfunction "GND_6") (pintype "power_in"))
      (node (ref "U2") (pin "1") (pinfunction "Ground_1") (pintype "power_in"))
      (node (ref "U3") (pin "12") (pinfunction "VSSA/VREF-_12") (pintype "power_in"))
      (node (ref "U3") (pin "18") (pinfunction "VSS_18") (pintype "power_in"))
      (node (ref "U3") (pin "31") (pinfunction "VSS_31") (pintype "power_in"))
      (node (ref "U3") (pin "47") (pinfunction "VSS_47") (pintype "power_in"))
      (node (ref "U3") (pin "63") (pinfunction "VSS_63") (pintype "power_in"))
      (node (ref "U5") (pin "2") (pinfunction "GND_2") (pintype "power_in"))
      (node (ref "U5") (pin "4") (pinfunction "GND_4") (pintype "power_in"))
      (node (ref "Y1") (pin "2") (pinfunction "GND_2") (pintype "power_in"))
      (node (ref "Y4") (pin "2") (pinfunction "GND_2") (pintype "power_in"))
    )
    (net (code "48") (name "Net-(DS1-A)") (class "Default")
      (node (ref "DS1") (pin "1") (pinfunction "A_1") (pintype "passive"))
      (node (ref "R3") (pin "2") (pinfunction "2_2") (pintype "power_in"))
    )
    (net (code "49") (name "Net-(DS1-K)") (class "Default")
      (node (ref "DS1") (pin "2") (pinfunction "K_2") (pintype "passive"))
      (node (ref "U3") (pin "38") (pinfunction "PC7_38") (pintype "bidirectional"))
    )
    (net (code "50") (name "Net-(DS2-A)") (class "Default")
      (node (ref "DS2") (pin "1") (pinfunction "A_1") (pintype "passive"))
      (node (ref "R5") (pin "2") (pinfunction "2_2") (pintype "power_in"))
    )
    (net (code "51") (name "Net-(DS2-K)") (class "Default")
      (node (ref "DS2") (pin "2") (pinfunction "K_2") (pintype "passive"))
      (node (ref "U3") (pin "39") (pinfunction "PC8_39") (pintype "bidirectional"))
    )
    (net (code "52") (name "Net-(DS3-A)") (class "Default")
      (node (ref "DS3") (pin "1") (pinfunction "A_1") (pintype "passive"))
      (node (ref "R17") (pin "2") (pinfunction "2_2") (pintype "power_in"))
    )
    (net (code "53") (name "Net-(DS3-K)") (class "Default")
      (node (ref "DS3") (pin "2") (pinfunction "K_2") (pintype "passive"))
      (node (ref "U3") (pin "40") (pinfunction "PC9_40") (pintype "bidirectional"))
    )
    (net (code "54") (name "Net-(DS4-A)") (class "Default")
      (node (ref "DS4") (pin "1") (pinfunction "A_1") (pintype "passive"))
      (node (ref "R15") (pin "2") (pinfunction "2_2") (pintype "power_in"))
    )
    (net (code "55") (name "Net-(DS4-K)") (class "Default")
      (node (ref "DS4") (pin "2") (pinfunction "K_2") (pintype "passive"))
      (node (ref "U3") (pin "41") (pinfunction "PA8_41") (pintype "bidirectional"))
    )
    (net (code "56") (name "Net-(DS5-A)") (class "Default")
      (node (ref "DS5") (pin "1") (pinfunction "A_1") (pintype "passive"))
      (node (ref "R19") (pin "2") (pinfunction "2_2") (pintype "power_in"))
    )
    (net (code "57") (name "Net-(DS5-K)") (class "Default")
      (node (ref "DS5") (pin "2") (pinfunction "K_2") (pintype "passive"))
      (node (ref "U3") (pin "42") (pinfunction "PA9_42") (pintype "bidirectional"))
    )
    (net (code "58") (name "Net-(DS6-A)") (class "Default")
      (node (ref "DS6") (pin "1") (pinfunction "A_1") (pintype "passive"))
      (node (ref "R22") (pin "2") (pinfunction "2_2") (pintype "power_in"))
    )
    (net (code "59") (name "Net-(DS6-K)") (class "Default")
      (node (ref "DS6") (pin "2") (pinfunction "K_2") (pintype "passive"))
      (node (ref "U3") (pin "43") (pinfunction "PA10_43") (pintype "bidirectional"))
    )
    (net (code "60") (name "Net-(J8-Pad3)") (class "Default")
      (node (ref "J8") (pin "3") (pinfunction "3_3") (pintype "passive"))
      (node (ref "R10") (pin "2") (pinfunction "2_2") (pintype "power_in"))
    )
    (net (code "61") (name "Net-(J8-Pad4)") (class "Default")
      (node (ref "J8") (pin "4") (pinfunction "4_4") (pintype "passive"))
      (node (ref "R7") (pin "2") (pinfunction "2_2") (pintype "power_in"))
    )
    (net (code "62") (name "Net-(Q1-D)") (class "Default")
      (node (ref "J5") (pin "1") (pinfunction "1_1") (pintype "passive"))
      (node (ref "Q1") (pin "5-6-7-8") (pinfunction "D_5-6-7-8") (pintype "passive"))
    )
    (net (code "63") (name "Net-(Q1-G)") (class "Default")
      (node (ref "Q1") (pin "4") (pinfunction "G_4") (pintype "passive"))
      (node (ref "R18") (pin "2") (pinfunction "2_2") (pintype "power_in"))
    )
    (net (code "64") (name "Net-(R7-Pad1)") (class "Default")
      (node (ref "R7") (pin "1") (pinfunction "1_1") (pintype "power_in"))
      (node (ref "R8") (pin "1") (pinfunction "1_1") (pintype "power_in"))
      (node (ref "R9") (pin "2") (pinfunction "2_2") (pintype "power_in"))
    )
    (net (code "65") (name "Net-(R10-Pad1)") (class "Default")
      (node (ref "R10") (pin "1") (pinfunction "1_1") (pintype "power_in"))
      (node (ref "R11") (pin "1") (pinfunction "1_1") (pintype "power_in"))
      (node (ref "R14") (pin "2") (pinfunction "2_2") (pintype "power_in"))
    )
    (net (code "66") (name "Net-(U1-CLK)") (class "Default")
      (node (ref "U1") (pin "5") (pinfunction "CLK_5") (pintype "input"))
      (node (ref "Y1") (pin "3") (pinfunction "Output_3") (pintype "passive"))
    )
    (net (code "67") (name "Net-(U3A-BOOT0)") (class "Default")
      (node (ref "R1") (pin "1") (pinfunction "1_1") (pintype "power_in"))
      (node (ref "R12") (pin "1") (pinfunction "1_1") (pintype "power_in"))
      (node (ref "U3") (pin "60") (pinfunction "BOOT0_60") (pintype "input"))
    )
    (net (code "68") (name "Net-(U3A-PC5)") (class "Default")
      (node (ref "C15") (pin "2") (pinfunction "2_2") (pintype "power_in"))
      (node (ref "R6") (pin "2") (pinfunction "2_2") (pintype "power_in"))
      (node (ref "U3") (pin "25") (pinfunction "PC5_25") (pintype "bidirectional"))
    )
    (net (code "69") (name "Net-(U3A-PH0-OSC_IN)") (class "Default")
      (node (ref "U3") (pin "5") (pinfunction "PH0-OSC_IN_5") (pintype "bidirectional"))
      (node (ref "Y4") (pin "3") (pinfunction "Output_3") (pintype "passive"))
    )
    (net (code "70") (name "Net-(U3A-VCAP1)") (class "Default")
      (node (ref "C32") (pin "2") (pinfunction "2_2") (pintype "power_in"))
      (node (ref "U3") (pin "30") (pinfunction "VCAP1_30") (pintype "power_in"))
    )
    (net (code "71") (name "unconnected-(J1-Pad3)") (class "Default")
      (node (ref "J1") (pin "3") (pinfunction "3_3") (pintype "passive"))
    )
    (net (code "72") (name "unconnected-(J1-Pad4)") (class "Default")
      (node (ref "J1") (pin "4") (pinfunction "4_4") (pintype "passive"))
    )
    (net (code "73") (name "unconnected-(J1-Pad5)") (class "Default")
      (node (ref "J1") (pin "5") (pinfunction "5_5") (pintype "passive"))
    )
    (net (code "74") (name "unconnected-(J1-Pad8)") (class "Default")
      (node (ref "J1") (pin "8") (pinfunction "8_8") (pintype "passive"))
    )
    (net (code "75") (name "unconnected-(J1-Pad9)") (class "Default")
      (node (ref "J1") (pin "9") (pinfunction "9_9") (pintype "passive"))
    )
    (net (code "76") (name "unconnected-(J2-Pad3)") (class "Default")
      (node (ref "J2") (pin "3") (pinfunction "3_3") (pintype "passive"))
    )
    (net (code "77") (name "unconnected-(J2-Pad4)") (class "Default")
      (node (ref "J2") (pin "4") (pinfunction "4_4") (pintype "passive"))
    )
    (net (code "78") (name "unconnected-(J2-Pad5)") (class "Default")
      (node (ref "J2") (pin "5") (pinfunction "5_5") (pintype "passive"))
    )
    (net (code "79") (name "unconnected-(J2-Pad8)") (class "Default")
      (node (ref "J2") (pin "8") (pinfunction "8_8") (pintype "passive"))
    )
    (net (code "80") (name "unconnected-(J2-Pad9)") (class "Default")
      (node (ref "J2") (pin "9") (pinfunction "9_9") (pintype "passive"))
    )
    (net (code "81") (name "unconnected-(J3-Pad5)") (class "Default")
      (node (ref "J3") (pin "5") (pinfunction "5_5") (pintype "passive"))
    )
    (net (code "82") (name "unconnected-(J3-Pad8)") (class "Default")
      (node (ref "J3") (pin "8") (pinfunction "8_8") (pintype "passive"))
    )
    (net (code "83") (name "unconnected-(J4-ID-Pad4)") (class "Default")
      (node (ref "J4") (pin "4") (pinfunction "ID_4") (pintype "passive+no_connect"))
    )
    (net (code "84") (name "unconnected-(J4-Shield-PadShell)") (class "Default")
      (node (ref "J4") (pin "Shell") (pinfunction "Shield_Shell") (pintype "passive+no_connect"))
    )
    (net (code "85") (name "unconnected-(J4-VBUS-Pad1)") (class "Default")
      (node (ref "J4") (pin "1") (pinfunction "VBUS_1") (pintype "passive+no_connect"))
    )
    (net (code "86") (name "unconnected-(J8-Pad5)") (class "Default")
      (node (ref "J8") (pin "5") (pinfunction "5_5") (pintype "passive"))
    )
    (net (code "87") (name "unconnected-(J8-Pad6)") (class "Default")
      (node (ref "J8") (pin "6") (pinfunction "6_6") (pintype "passive"))
    )
    (net (code "88") (name "unconnected-(J8-Pad7)") (class "Default")
      (node (ref "J8") (pin "7") (pinfunction "7_7") (pintype "passive"))
    )
    (net (code "89") (name "unconnected-(J8-Pad8)") (class "Default")
      (node (ref "J8") (pin "8") (pinfunction "8_8") (pintype "passive"))
    )
    (net (code "90") (name "unconnected-(J8-Pad9)") (class "Default")
      (node (ref "J8") (pin "9") (pinfunction "9_9") (pintype "passive"))
    )
    (net (code "91") (name "unconnected-(P1-Pad11)") (class "Default")
      (node (ref "P1") (pin "11") (pinfunction "11_11") (pintype "passive+no_connect"))
    )
    (net (code "92") (name "unconnected-(P1-Pad17)") (class "Default")
      (node (ref "P1") (pin "17") (pinfunction "17_17") (pintype "passive+no_connect"))
    )
    (net (code "93") (name "unconnected-(P1-Pad19)") (class "Default")
      (node (ref "P1") (pin "19") (pinfunction "19_19") (pintype "passive+no_connect"))
    )
    (net (code "94") (name "unconnected-(U1-NC-Pad9)") (class "Default")
      (node (ref "U1") (pin "9") (pinfunction "NC_9") (pintype "passive+no_connect"))
    )
    (net (code "95") (name "unconnected-(U1-NC-Pad11)") (class "Default")
      (node (ref "U1") (pin "11") (pinfunction "NC_11") (pintype "passive+no_connect"))
    )
    (net (code "96") (name "unconnected-(U1-NC-Pad16)") (class "Default")
      (node (ref "U1") (pin "16") (pinfunction "NC_16") (pintype "passive+no_connect"))
    )
    (net (code "97") (name "unconnected-(U1-NC-Pad24)") (class "Default")
      (node (ref "U1") (pin "24") (pinfunction "NC_24") (pintype "passive+no_connect"))
    )
    (net (code "98") (name "unconnected-(U1-NC-Pad26)") (class "Default")
      (node (ref "U1") (pin "26") (pinfunction "NC_26") (pintype "passive+no_connect"))
    )
    (net (code "99") (name "unconnected-(U1-NC-Pad32)") (class "Default")
      (node (ref "U1") (pin "32") (pinfunction "NC_32") (pintype "passive+no_connect"))
    )
    (net (code "100") (name "unconnected-(U1-POSCMP-Pad30)") (class "Default")
      (node (ref "U1") (pin "30") (pinfunction "POSCMP_30") (pintype "output+no_connect"))
    )
    (net (code "101") (name "unconnected-(U1-REF1-Pad31)") (class "Default")
      (node (ref "U1") (pin "31") (pinfunction "REF1_31") (pintype "input+no_connect"))
    )
    (net (code "102") (name "unconnected-(U1-REF2-Pad1)") (class "Default")
      (node (ref "U1") (pin "1") (pinfunction "REF2_1") (pintype "input+no_connect"))
    )
    (net (code "103") (name "unconnected-(U1-REF3-Pad2)") (class "Default")
      (node (ref "U1") (pin "2") (pinfunction "REF3_2") (pintype "input+no_connect"))
    )
    (net (code "104") (name "unconnected-(U1-REFR1-Pad28)") (class "Default")
      (node (ref "U1") (pin "28") (pinfunction "REFR1_28") (pintype "input+no_connect"))
    )
    (net (code "105") (name "unconnected-(U1-REFR2-Pad13)") (class "Default")
      (node (ref "U1") (pin "13") (pinfunction "REFR2_13") (pintype "input+no_connect"))
    )
    (net (code "106") (name "unconnected-(U1-REFR3-Pad29)") (class "Default")
      (node (ref "U1") (pin "29") (pinfunction "REFR3_29") (pintype "input+no_connect"))
    )
    (net (code "107") (name "unconnected-(U3A-PA0-WKUP-Pad14)") (class "Default")
      (node (ref "U3") (pin "14") (pinfunction "PA0-WKUP_14") (pintype "bidirectional"))
    )
    (net (code "108") (name "unconnected-(U3A-PA4-Pad20)") (class "Default")
      (node (ref "U3") (pin "20") (pinfunction "PA4_20") (pintype "bidirectional+no_connect"))
    )
    (net (code "109") (name "unconnected-(U3A-PB0-Pad26)") (class "Default")
      (node (ref "U3") (pin "26") (pinfunction "PB0_26") (pintype "bidirectional+no_connect"))
    )
    (net (code "110") (name "unconnected-(U3A-PB1-Pad27)") (class "Default")
      (node (ref "U3") (pin "27") (pinfunction "PB1_27") (pintype "bidirectional+no_connect"))
    )
    (net (code "111") (name "unconnected-(U3A-PB2-Pad28)") (class "Default")
      (node (ref "U3") (pin "28") (pinfunction "PB2_28") (pintype "bidirectional+no_connect"))
    )
    (net (code "112") (name "unconnected-(U3A-PB8-Pad61)") (class "Default")
      (node (ref "U3") (pin "61") (pinfunction "PB8_61") (pintype "bidirectional+no_connect"))
    )
    (net (code "113") (name "unconnected-(U3A-PB9-Pad62)") (class "Default")
      (node (ref "U3") (pin "62") (pinfunction "PB9_62") (pintype "bidirectional"))
    )
    (net (code "114") (name "unconnected-(U3A-PB10-Pad29)") (class "Default")
      (node (ref "U3") (pin "29") (pinfunction "PB10_29") (pintype "bidirectional+no_connect"))
    )
    (net (code "115") (name "unconnected-(U3A-PB12-Pad33)") (class "Default")
      (node (ref "U3") (pin "33") (pinfunction "PB12_33") (pintype "bidirectional+no_connect"))
    )
    (net (code "116") (name "unconnected-(U3A-PB13-Pad34)") (class "Default")
      (node (ref "U3") (pin "34") (pinfunction "PB13_34") (pintype "bidirectional+no_connect"))
    )
    (net (code "117") (name "unconnected-(U3A-PB14-Pad35)") (class "Default")
      (node (ref "U3") (pin "35") (pinfunction "PB14_35") (pintype "bidirectional+no_connect"))
    )
    (net (code "118") (name "unconnected-(U3A-PC0-Pad8)") (class "Default")
      (node (ref "U3") (pin "8") (pinfunction "PC0_8") (pintype "bidirectional"))
    )
    (net (code "119") (name "unconnected-(U3A-PC1-Pad9)") (class "Default")
      (node (ref "U3") (pin "9") (pinfunction "PC1_9") (pintype "bidirectional"))
    )
    (net (code "120") (name "unconnected-(U3A-PC3-Pad11)") (class "Default")
      (node (ref "U3") (pin "11") (pinfunction "PC3_11") (pintype "bidirectional"))
    )
    (net (code "121") (name "unconnected-(U3A-PC4-Pad24)") (class "Default")
      (node (ref "U3") (pin "24") (pinfunction "PC4_24") (pintype "bidirectional+no_connect"))
    )
    (net (code "122") (name "unconnected-(U3A-PC14-OSC32_IN-Pad3)") (class "Default")
      (node (ref "U3") (pin "3") (pinfunction "PC14-OSC32_IN_3") (pintype "bidirectional"))
    )
    (net (code "123") (name "unconnected-(U3A-PC15-OSC32_OUT-Pad4)") (class "Default")
      (node (ref "U3") (pin "4") (pinfunction "PC15-OSC32_OUT_4") (pintype "bidirectional"))
    )
    (net (code "124") (name "unconnected-(U3A-PD2-Pad54)") (class "Default")
      (node (ref "U3") (pin "54") (pinfunction "PD2_54") (pintype "bidirectional+no_connect"))
    )
    (net (code "125") (name "unconnected-(U3A-PH1-OSC_OUT-Pad6)") (class "Default")
      (node (ref "U3") (pin "6") (pinfunction "PH1-OSC_OUT_6") (pintype "bidirectional+no_connect"))
    )
  )
)
